# shifter.net
KiCad netlist of a schematic drawn in EAGLE
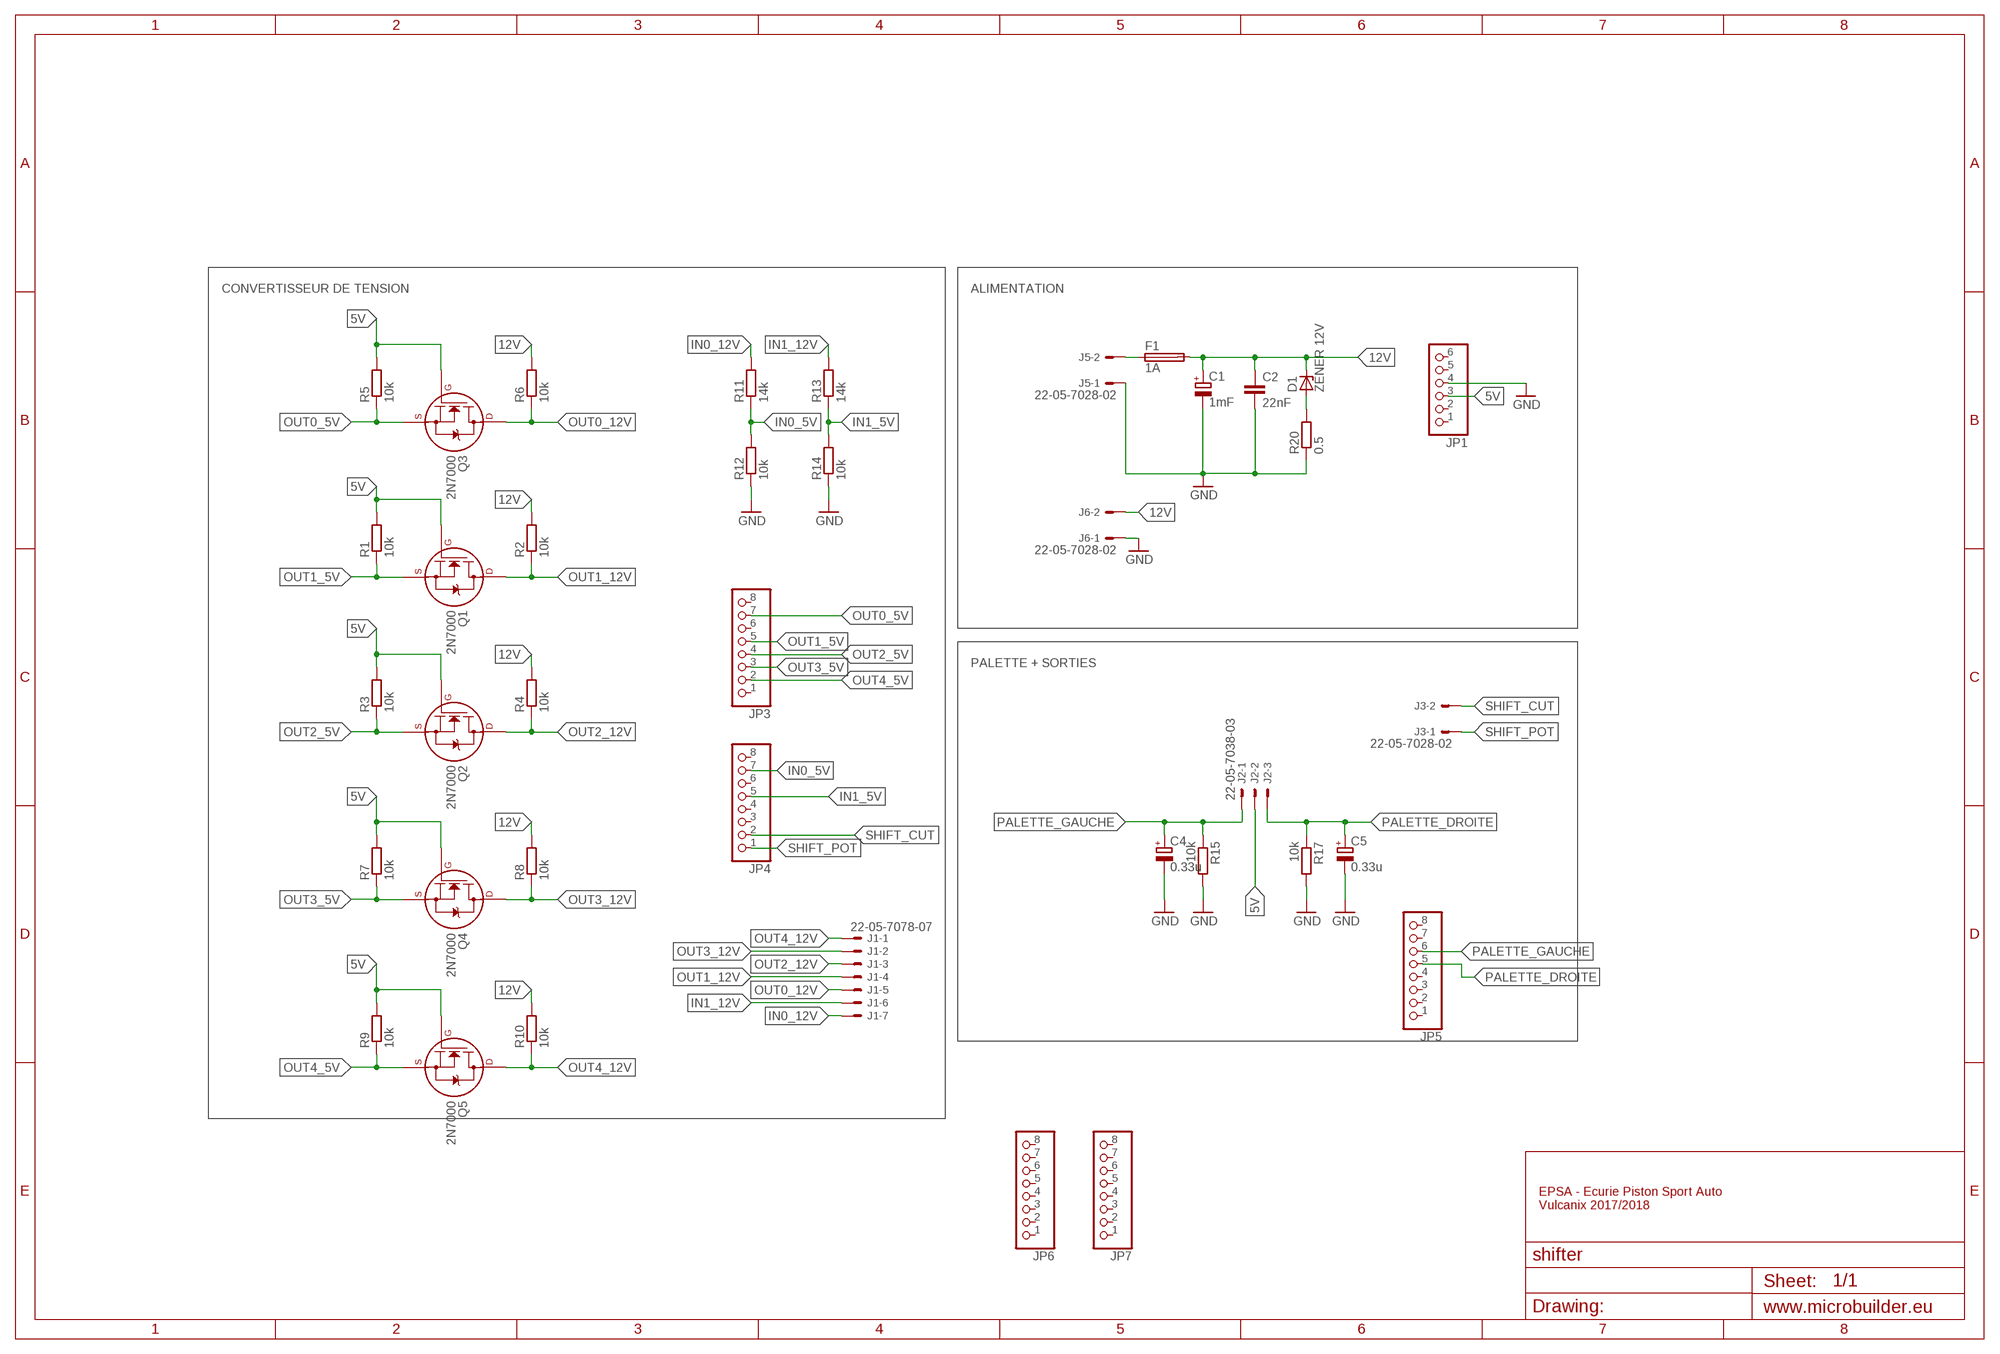
[diagram p0: schematic, sheet 1]

(export (version "E")
  (design (tool "Eeschema 10.0.6"))
  (components
    (comp (ref "C1")
      (value "1mF")
      (footprint "eagle-import:E7,5-16")
      (libsource (lib "eagle-import") (part "rcl_334_CPOL-EUE7.5-16"))
    )
    (comp (ref "C2")
      (value "22nF")
      (footprint "eagle-import:C025-025X050")
      (libsource (lib "eagle-import") (part "C-EU025-025X050"))
    )
    (comp (ref "C4")
      (value "0.33u")
      (footprint "eagle-import:E2,5-6E")
      (libsource (lib "eagle-import") (part "CPOL-EUE2,5-6E"))
    )
    (comp (ref "C5")
      (value "0.33u")
      (footprint "eagle-import:E2,5-6E")
      (libsource (lib "eagle-import") (part "CPOL-EUE2,5-6E"))
    )
    (comp (ref "D1")
      (value "ZENER 12V")
      (footprint "eagle-import:DO41Z10")
      (libsource (lib "eagle-import") (part "ZENER-DIODEDO41Z10"))
    )
    (comp (ref "F1")
      (value "1A")
      (footprint "eagle-import:SH25")
      (fields (field (name "MF") "SCHURTER") (field (name "MPN") "0031.8211"))
      (libsource (lib "eagle-import") (part "SH25"))
    )
    (comp (ref "J1")
      (value "22-05-7078-07")
      (footprint "eagle-import:7395-07")
      (libsource (lib "eagle-import") (part "22-?-0705-7078"))
    )
    (comp (ref "J2")
      (value "22-05-7038-03")
      (footprint "eagle-import:7395-03")
      (libsource (lib "eagle-import") (part "22-?-0305-7038"))
    )
    (comp (ref "J3")
      (value "22-05-7028-02")
      (footprint "eagle-import:7395-02")
      (libsource (lib "eagle-import") (part "22-?-0205-7028"))
    )
    (comp (ref "J5")
      (value "22-05-7028-02")
      (footprint "eagle-import:7395-02")
      (libsource (lib "eagle-import") (part "22-?-0205-7028"))
    )
    (comp (ref "J6")
      (value "22-05-7028-02")
      (footprint "eagle-import:7395-02")
      (libsource (lib "eagle-import") (part "22-?-0205-7028"))
    )
    (comp (ref "JP1")
      (value "HEADER-1X6")
      (footprint "eagle-import:1X06_OVAL")
      (libsource (lib "eagle-import") (part "HEADER-1X6"))
    )
    (comp (ref "JP3")
      (value "HEADER-1X8")
      (footprint "eagle-import:1X08_OVAL")
      (libsource (lib "eagle-import") (part "HEADER-1X8"))
    )
    (comp (ref "JP4")
      (value "HEADER-1X8")
      (footprint "eagle-import:1X08_OVAL")
      (libsource (lib "eagle-import") (part "HEADER-1X8"))
    )
    (comp (ref "JP5")
      (value "PINHD-1X8")
      (footprint "eagle-import:1X08")
      (libsource (lib "eagle-import") (part "PINHD-1X8"))
    )
    (comp (ref "JP6")
      (value "PINHD-1X8")
      (footprint "eagle-import:1X08")
      (libsource (lib "eagle-import") (part "PINHD-1X8"))
    )
    (comp (ref "JP7")
      (value "PINHD-1X8")
      (footprint "eagle-import:1X08")
      (libsource (lib "eagle-import") (part "PINHD-1X8"))
    )
    (comp (ref "Q1")
      (value "2N7000")
      (footprint "eagle-import:TO-92")
      (libsource (lib "eagle-import") (part "2N700_TO920"))
    )
    (comp (ref "Q2")
      (value "2N7000")
      (footprint "eagle-import:TO-92")
      (libsource (lib "eagle-import") (part "2N700_TO920"))
    )
    (comp (ref "Q3")
      (value "2N7000")
      (footprint "eagle-import:TO-92")
      (libsource (lib "eagle-import") (part "2N700_TO920"))
    )
    (comp (ref "Q4")
      (value "2N7000")
      (footprint "eagle-import:TO-92")
      (libsource (lib "eagle-import") (part "2N700_TO920"))
    )
    (comp (ref "Q5")
      (value "2N7000")
      (footprint "eagle-import:TO-92")
      (libsource (lib "eagle-import") (part "2N700_TO920"))
    )
    (comp (ref "R1")
      (value "10k")
      (footprint "eagle-import:0204_7")
      (libsource (lib "eagle-import") (part "R-EU_0204/7"))
    )
    (comp (ref "R2")
      (value "10k")
      (footprint "eagle-import:0204_7")
      (libsource (lib "eagle-import") (part "R-EU_0204/7"))
    )
    (comp (ref "R3")
      (value "10k")
      (footprint "eagle-import:0204_7")
      (libsource (lib "eagle-import") (part "R-EU_0204/7"))
    )
    (comp (ref "R4")
      (value "10k")
      (footprint "eagle-import:0204_7")
      (libsource (lib "eagle-import") (part "R-EU_0204/7"))
    )
    (comp (ref "R5")
      (value "10k")
      (footprint "eagle-import:0204_7")
      (libsource (lib "eagle-import") (part "R-EU_0204/7"))
    )
    (comp (ref "R6")
      (value "10k")
      (footprint "eagle-import:0204_7")
      (libsource (lib "eagle-import") (part "R-EU_0204/7"))
    )
    (comp (ref "R7")
      (value "10k")
      (footprint "eagle-import:0204_7")
      (libsource (lib "eagle-import") (part "R-EU_0204/7"))
    )
    (comp (ref "R8")
      (value "10k")
      (footprint "eagle-import:0204_7")
      (libsource (lib "eagle-import") (part "R-EU_0204/7"))
    )
    (comp (ref "R9")
      (value "10k")
      (footprint "eagle-import:0204_7")
      (libsource (lib "eagle-import") (part "R-EU_0204/7"))
    )
    (comp (ref "R10")
      (value "10k")
      (footprint "eagle-import:0204_7")
      (libsource (lib "eagle-import") (part "R-EU_0204/7"))
    )
    (comp (ref "R11")
      (value "14k")
      (footprint "eagle-import:0204_7")
      (libsource (lib "eagle-import") (part "R-EU_0204/7"))
    )
    (comp (ref "R12")
      (value "10k")
      (footprint "eagle-import:0204_7")
      (libsource (lib "eagle-import") (part "R-EU_0204/7"))
    )
    (comp (ref "R13")
      (value "14k")
      (footprint "eagle-import:0204_7")
      (libsource (lib "eagle-import") (part "R-EU_0204/7"))
    )
    (comp (ref "R14")
      (value "10k")
      (footprint "eagle-import:0204_7")
      (libsource (lib "eagle-import") (part "R-EU_0204/7"))
    )
    (comp (ref "R15")
      (value "10k")
      (footprint "eagle-import:0204_7")
      (libsource (lib "eagle-import") (part "R-EU_0204/7"))
    )
    (comp (ref "R17")
      (value "10k")
      (footprint "eagle-import:0204_7")
      (libsource (lib "eagle-import") (part "R-EU_0204/7"))
    )
    (comp (ref "R20")
      (value "0.5")
      (footprint "eagle-import:0309_12")
      (libsource (lib "eagle-import") (part "R-EU_0309/12"))
    )
  )
  (nets
    (net (code "1") (name "5V") (class "Default")
      (node (ref "J2") (pin "2") (pinfunction "S_2") (pintype "passive"))
      (node (ref "JP1") (pin "3") (pinfunction "3_3") (pintype "passive"))
      (node (ref "Q1") (pin "2") (pinfunction "G_2") (pintype "tri_state"))
      (node (ref "Q2") (pin "2") (pinfunction "G_2") (pintype "tri_state"))
      (node (ref "Q3") (pin "2") (pinfunction "G_2") (pintype "tri_state"))
      (node (ref "Q4") (pin "2") (pinfunction "G_2") (pintype "tri_state"))
      (node (ref "Q5") (pin "2") (pinfunction "G_2") (pintype "tri_state"))
      (node (ref "R1") (pin "2") (pinfunction "2_2") (pintype "passive"))
      (node (ref "R3") (pin "2") (pinfunction "2_2") (pintype "passive"))
      (node (ref "R5") (pin "2") (pinfunction "2_2") (pintype "passive"))
      (node (ref "R7") (pin "2") (pinfunction "2_2") (pintype "passive"))
      (node (ref "R9") (pin "2") (pinfunction "2_2") (pintype "passive"))
    )
    (net (code "2") (name "12V") (class "Default")
      (node (ref "C1") (pin "+") (pinfunction "+_+") (pintype "passive"))
      (node (ref "C2") (pin "1") (pinfunction "1_1") (pintype "passive"))
      (node (ref "D1") (pin "C") (pinfunction "C_C") (pintype "passive"))
      (node (ref "F1") (pin "2") (pinfunction "2_2") (pintype "passive"))
      (node (ref "J6") (pin "2") (pinfunction "S_2") (pintype "passive"))
      (node (ref "R10") (pin "2") (pinfunction "2_2") (pintype "passive"))
      (node (ref "R2") (pin "2") (pinfunction "2_2") (pintype "passive"))
      (node (ref "R4") (pin "2") (pinfunction "2_2") (pintype "passive"))
      (node (ref "R6") (pin "2") (pinfunction "2_2") (pintype "passive"))
      (node (ref "R8") (pin "2") (pinfunction "2_2") (pintype "passive"))
    )
    (net (code "3") (name "GND") (class "Default")
      (node (ref "C1") (pin "-") (pinfunction "-_-") (pintype "passive"))
      (node (ref "C2") (pin "2") (pinfunction "2_2") (pintype "passive"))
      (node (ref "C4") (pin "-") (pinfunction "-_-") (pintype "passive"))
      (node (ref "C5") (pin "-") (pinfunction "-_-") (pintype "passive"))
      (node (ref "J5") (pin "1") (pinfunction "S_1") (pintype "passive"))
      (node (ref "J6") (pin "1") (pinfunction "S_1") (pintype "passive"))
      (node (ref "JP1") (pin "4") (pinfunction "4_4") (pintype "passive"))
      (node (ref "R12") (pin "1") (pinfunction "1_1") (pintype "passive"))
      (node (ref "R14") (pin "1") (pinfunction "1_1") (pintype "passive"))
      (node (ref "R15") (pin "2") (pinfunction "2_2") (pintype "passive"))
      (node (ref "R17") (pin "2") (pinfunction "2_2") (pintype "passive"))
      (node (ref "R20") (pin "1") (pinfunction "1_1") (pintype "passive"))
    )
    (net (code "4") (name "IN0_5V") (class "Default")
      (node (ref "JP4") (pin "7") (pinfunction "7_7") (pintype "passive"))
      (node (ref "R11") (pin "1") (pinfunction "1_1") (pintype "passive"))
      (node (ref "R12") (pin "2") (pinfunction "2_2") (pintype "passive"))
    )
    (net (code "5") (name "IN0_12V") (class "Default")
      (node (ref "J1") (pin "7") (pinfunction "S_7") (pintype "passive"))
      (node (ref "R11") (pin "2") (pinfunction "2_2") (pintype "passive"))
    )
    (net (code "6") (name "IN1_5V") (class "Default")
      (node (ref "JP4") (pin "5") (pinfunction "5_5") (pintype "passive"))
      (node (ref "R13") (pin "1") (pinfunction "1_1") (pintype "passive"))
      (node (ref "R14") (pin "2") (pinfunction "2_2") (pintype "passive"))
    )
    (net (code "7") (name "IN1_12V") (class "Default")
      (node (ref "J1") (pin "6") (pinfunction "S_6") (pintype "passive"))
      (node (ref "R13") (pin "2") (pinfunction "2_2") (pintype "passive"))
    )
    (net (code "8") (name "Net-(D1-PadA)") (class "Default")
      (node (ref "D1") (pin "A") (pinfunction "A_A") (pintype "passive"))
      (node (ref "R20") (pin "2") (pinfunction "2_2") (pintype "passive"))
    )
    (net (code "9") (name "Net-(J5B-S)") (class "Default")
      (node (ref "F1") (pin "1") (pinfunction "1_1") (pintype "passive"))
      (node (ref "J5") (pin "2") (pinfunction "S_2") (pintype "passive"))
    )
    (net (code "10") (name "OUT0_5V") (class "Default")
      (node (ref "JP3") (pin "7") (pinfunction "7_7") (pintype "passive"))
      (node (ref "Q3") (pin "1") (pinfunction "S_1") (pintype "bidirectional"))
      (node (ref "R5") (pin "1") (pinfunction "1_1") (pintype "passive"))
    )
    (net (code "11") (name "OUT0_12V") (class "Default")
      (node (ref "J1") (pin "5") (pinfunction "S_5") (pintype "passive"))
      (node (ref "Q3") (pin "3") (pinfunction "D_3") (pintype "bidirectional"))
      (node (ref "R6") (pin "1") (pinfunction "1_1") (pintype "passive"))
    )
    (net (code "12") (name "OUT1_5V") (class "Default")
      (node (ref "JP3") (pin "5") (pinfunction "5_5") (pintype "passive"))
      (node (ref "Q1") (pin "1") (pinfunction "S_1") (pintype "bidirectional"))
      (node (ref "R1") (pin "1") (pinfunction "1_1") (pintype "passive"))
    )
    (net (code "13") (name "OUT1_12V") (class "Default")
      (node (ref "J1") (pin "4") (pinfunction "S_4") (pintype "passive"))
      (node (ref "Q1") (pin "3") (pinfunction "D_3") (pintype "bidirectional"))
      (node (ref "R2") (pin "1") (pinfunction "1_1") (pintype "passive"))
    )
    (net (code "14") (name "OUT2_5V") (class "Default")
      (node (ref "JP3") (pin "4") (pinfunction "4_4") (pintype "passive"))
      (node (ref "Q2") (pin "1") (pinfunction "S_1") (pintype "bidirectional"))
      (node (ref "R3") (pin "1") (pinfunction "1_1") (pintype "passive"))
    )
    (net (code "15") (name "OUT2_12V") (class "Default")
      (node (ref "J1") (pin "3") (pinfunction "S_3") (pintype "passive"))
      (node (ref "Q2") (pin "3") (pinfunction "D_3") (pintype "bidirectional"))
      (node (ref "R4") (pin "1") (pinfunction "1_1") (pintype "passive"))
    )
    (net (code "16") (name "OUT3_5V") (class "Default")
      (node (ref "JP3") (pin "3") (pinfunction "3_3") (pintype "passive"))
      (node (ref "Q4") (pin "1") (pinfunction "S_1") (pintype "bidirectional"))
      (node (ref "R7") (pin "1") (pinfunction "1_1") (pintype "passive"))
    )
    (net (code "17") (name "OUT3_12V") (class "Default")
      (node (ref "J1") (pin "2") (pinfunction "S_2") (pintype "passive"))
      (node (ref "Q4") (pin "3") (pinfunction "D_3") (pintype "bidirectional"))
      (node (ref "R8") (pin "1") (pinfunction "1_1") (pintype "passive"))
    )
    (net (code "18") (name "OUT4_5V") (class "Default")
      (node (ref "JP3") (pin "2") (pinfunction "2_2") (pintype "passive"))
      (node (ref "Q5") (pin "1") (pinfunction "S_1") (pintype "bidirectional"))
      (node (ref "R9") (pin "1") (pinfunction "1_1") (pintype "passive"))
    )
    (net (code "19") (name "OUT4_12V") (class "Default")
      (node (ref "J1") (pin "1") (pinfunction "S_1") (pintype "passive"))
      (node (ref "Q5") (pin "3") (pinfunction "D_3") (pintype "bidirectional"))
      (node (ref "R10") (pin "1") (pinfunction "1_1") (pintype "passive"))
    )
    (net (code "20") (name "PALETTE_DROITE") (class "Default")
      (node (ref "C5") (pin "+") (pinfunction "+_+") (pintype "passive"))
      (node (ref "J2") (pin "3") (pinfunction "S_3") (pintype "passive"))
      (node (ref "JP5") (pin "5") (pinfunction "5_5") (pintype "passive"))
      (node (ref "R17") (pin "1") (pinfunction "1_1") (pintype "passive"))
    )
    (net (code "21") (name "PALETTE_GAUCHE") (class "Default")
      (node (ref "C4") (pin "+") (pinfunction "+_+") (pintype "passive"))
      (node (ref "J2") (pin "1") (pinfunction "S_1") (pintype "passive"))
      (node (ref "JP5") (pin "6") (pinfunction "6_6") (pintype "passive"))
      (node (ref "R15") (pin "1") (pinfunction "1_1") (pintype "passive"))
    )
    (net (code "22") (name "SHIFT_CUT") (class "Default")
      (node (ref "J3") (pin "2") (pinfunction "S_2") (pintype "passive"))
      (node (ref "JP4") (pin "2") (pinfunction "2_2") (pintype "passive"))
    )
    (net (code "23") (name "SHIFT_POT") (class "Default")
      (node (ref "J3") (pin "1") (pinfunction "S_1") (pintype "passive"))
      (node (ref "JP4") (pin "1") (pinfunction "1_1") (pintype "passive"))
    )
    (net (code "24") (name "unconnected-(JP1-Pad1)") (class "Default")
      (node (ref "JP1") (pin "1") (pinfunction "1_1") (pintype "passive"))
    )
    (net (code "25") (name "unconnected-(JP1-Pad2)") (class "Default")
      (node (ref "JP1") (pin "2") (pinfunction "2_2") (pintype "passive"))
    )
    (net (code "26") (name "unconnected-(JP1-Pad5)") (class "Default")
      (node (ref "JP1") (pin "5") (pinfunction "5_5") (pintype "passive"))
    )
    (net (code "27") (name "unconnected-(JP1-Pad6)") (class "Default")
      (node (ref "JP1") (pin "6") (pinfunction "6_6") (pintype "passive"))
    )
    (net (code "28") (name "unconnected-(JP3-Pad1)") (class "Default")
      (node (ref "JP3") (pin "1") (pinfunction "1_1") (pintype "passive"))
    )
    (net (code "29") (name "unconnected-(JP3-Pad6)") (class "Default")
      (node (ref "JP3") (pin "6") (pinfunction "6_6") (pintype "passive"))
    )
    (net (code "30") (name "unconnected-(JP3-Pad8)") (class "Default")
      (node (ref "JP3") (pin "8") (pinfunction "8_8") (pintype "passive"))
    )
    (net (code "31") (name "unconnected-(JP4-Pad3)") (class "Default")
      (node (ref "JP4") (pin "3") (pinfunction "3_3") (pintype "passive"))
    )
    (net (code "32") (name "unconnected-(JP4-Pad4)") (class "Default")
      (node (ref "JP4") (pin "4") (pinfunction "4_4") (pintype "passive"))
    )
    (net (code "33") (name "unconnected-(JP4-Pad6)") (class "Default")
      (node (ref "JP4") (pin "6") (pinfunction "6_6") (pintype "passive"))
    )
    (net (code "34") (name "unconnected-(JP4-Pad8)") (class "Default")
      (node (ref "JP4") (pin "8") (pinfunction "8_8") (pintype "passive"))
    )
    (net (code "35") (name "unconnected-(JP5-Pad1)") (class "Default")
      (node (ref "JP5") (pin "1") (pinfunction "1_1") (pintype "passive"))
    )
    (net (code "36") (name "unconnected-(JP5-Pad2)") (class "Default")
      (node (ref "JP5") (pin "2") (pinfunction "2_2") (pintype "passive"))
    )
    (net (code "37") (name "unconnected-(JP5-Pad3)") (class "Default")
      (node (ref "JP5") (pin "3") (pinfunction "3_3") (pintype "passive"))
    )
    (net (code "38") (name "unconnected-(JP5-Pad4)") (class "Default")
      (node (ref "JP5") (pin "4") (pinfunction "4_4") (pintype "passive"))
    )
    (net (code "39") (name "unconnected-(JP5-Pad7)") (class "Default")
      (node (ref "JP5") (pin "7") (pinfunction "7_7") (pintype "passive"))
    )
    (net (code "40") (name "unconnected-(JP5-Pad8)") (class "Default")
      (node (ref "JP5") (pin "8") (pinfunction "8_8") (pintype "passive"))
    )
    (net (code "41") (name "unconnected-(JP6-Pad1)") (class "Default")
      (node (ref "JP6") (pin "1") (pinfunction "1_1") (pintype "passive"))
    )
    (net (code "42") (name "unconnected-(JP6-Pad2)") (class "Default")
      (node (ref "JP6") (pin "2") (pinfunction "2_2") (pintype "passive"))
    )
    (net (code "43") (name "unconnected-(JP6-Pad3)") (class "Default")
      (node (ref "JP6") (pin "3") (pinfunction "3_3") (pintype "passive"))
    )
    (net (code "44") (name "unconnected-(JP6-Pad4)") (class "Default")
      (node (ref "JP6") (pin "4") (pinfunction "4_4") (pintype "passive"))
    )
    (net (code "45") (name "unconnected-(JP6-Pad5)") (class "Default")
      (node (ref "JP6") (pin "5") (pinfunction "5_5") (pintype "passive"))
    )
    (net (code "46") (name "unconnected-(JP6-Pad6)") (class "Default")
      (node (ref "JP6") (pin "6") (pinfunction "6_6") (pintype "passive"))
    )
    (net (code "47") (name "unconnected-(JP6-Pad7)") (class "Default")
      (node (ref "JP6") (pin "7") (pinfunction "7_7") (pintype "passive"))
    )
    (net (code "48") (name "unconnected-(JP6-Pad8)") (class "Default")
      (node (ref "JP6") (pin "8") (pinfunction "8_8") (pintype "passive"))
    )
    (net (code "49") (name "unconnected-(JP7-Pad1)") (class "Default")
      (node (ref "JP7") (pin "1") (pinfunction "1_1") (pintype "passive"))
    )
    (net (code "50") (name "unconnected-(JP7-Pad2)") (class "Default")
      (node (ref "JP7") (pin "2") (pinfunction "2_2") (pintype "passive"))
    )
    (net (code "51") (name "unconnected-(JP7-Pad3)") (class "Default")
      (node (ref "JP7") (pin "3") (pinfunction "3_3") (pintype "passive"))
    )
    (net (code "52") (name "unconnected-(JP7-Pad4)") (class "Default")
      (node (ref "JP7") (pin "4") (pinfunction "4_4") (pintype "passive"))
    )
    (net (code "53") (name "unconnected-(JP7-Pad5)") (class "Default")
      (node (ref "JP7") (pin "5") (pinfunction "5_5") (pintype "passive"))
    )
    (net (code "54") (name "unconnected-(JP7-Pad6)") (class "Default")
      (node (ref "JP7") (pin "6") (pinfunction "6_6") (pintype "passive"))
    )
    (net (code "55") (name "unconnected-(JP7-Pad7)") (class "Default")
      (node (ref "JP7") (pin "7") (pinfunction "7_7") (pintype "passive"))
    )
    (net (code "56") (name "unconnected-(JP7-Pad8)") (class "Default")
      (node (ref "JP7") (pin "8") (pinfunction "8_8") (pintype "passive"))
    )
  )
)
